# batteryholder3S2P_revA.net
KiCad netlist of a schematic drawn in EAGLE
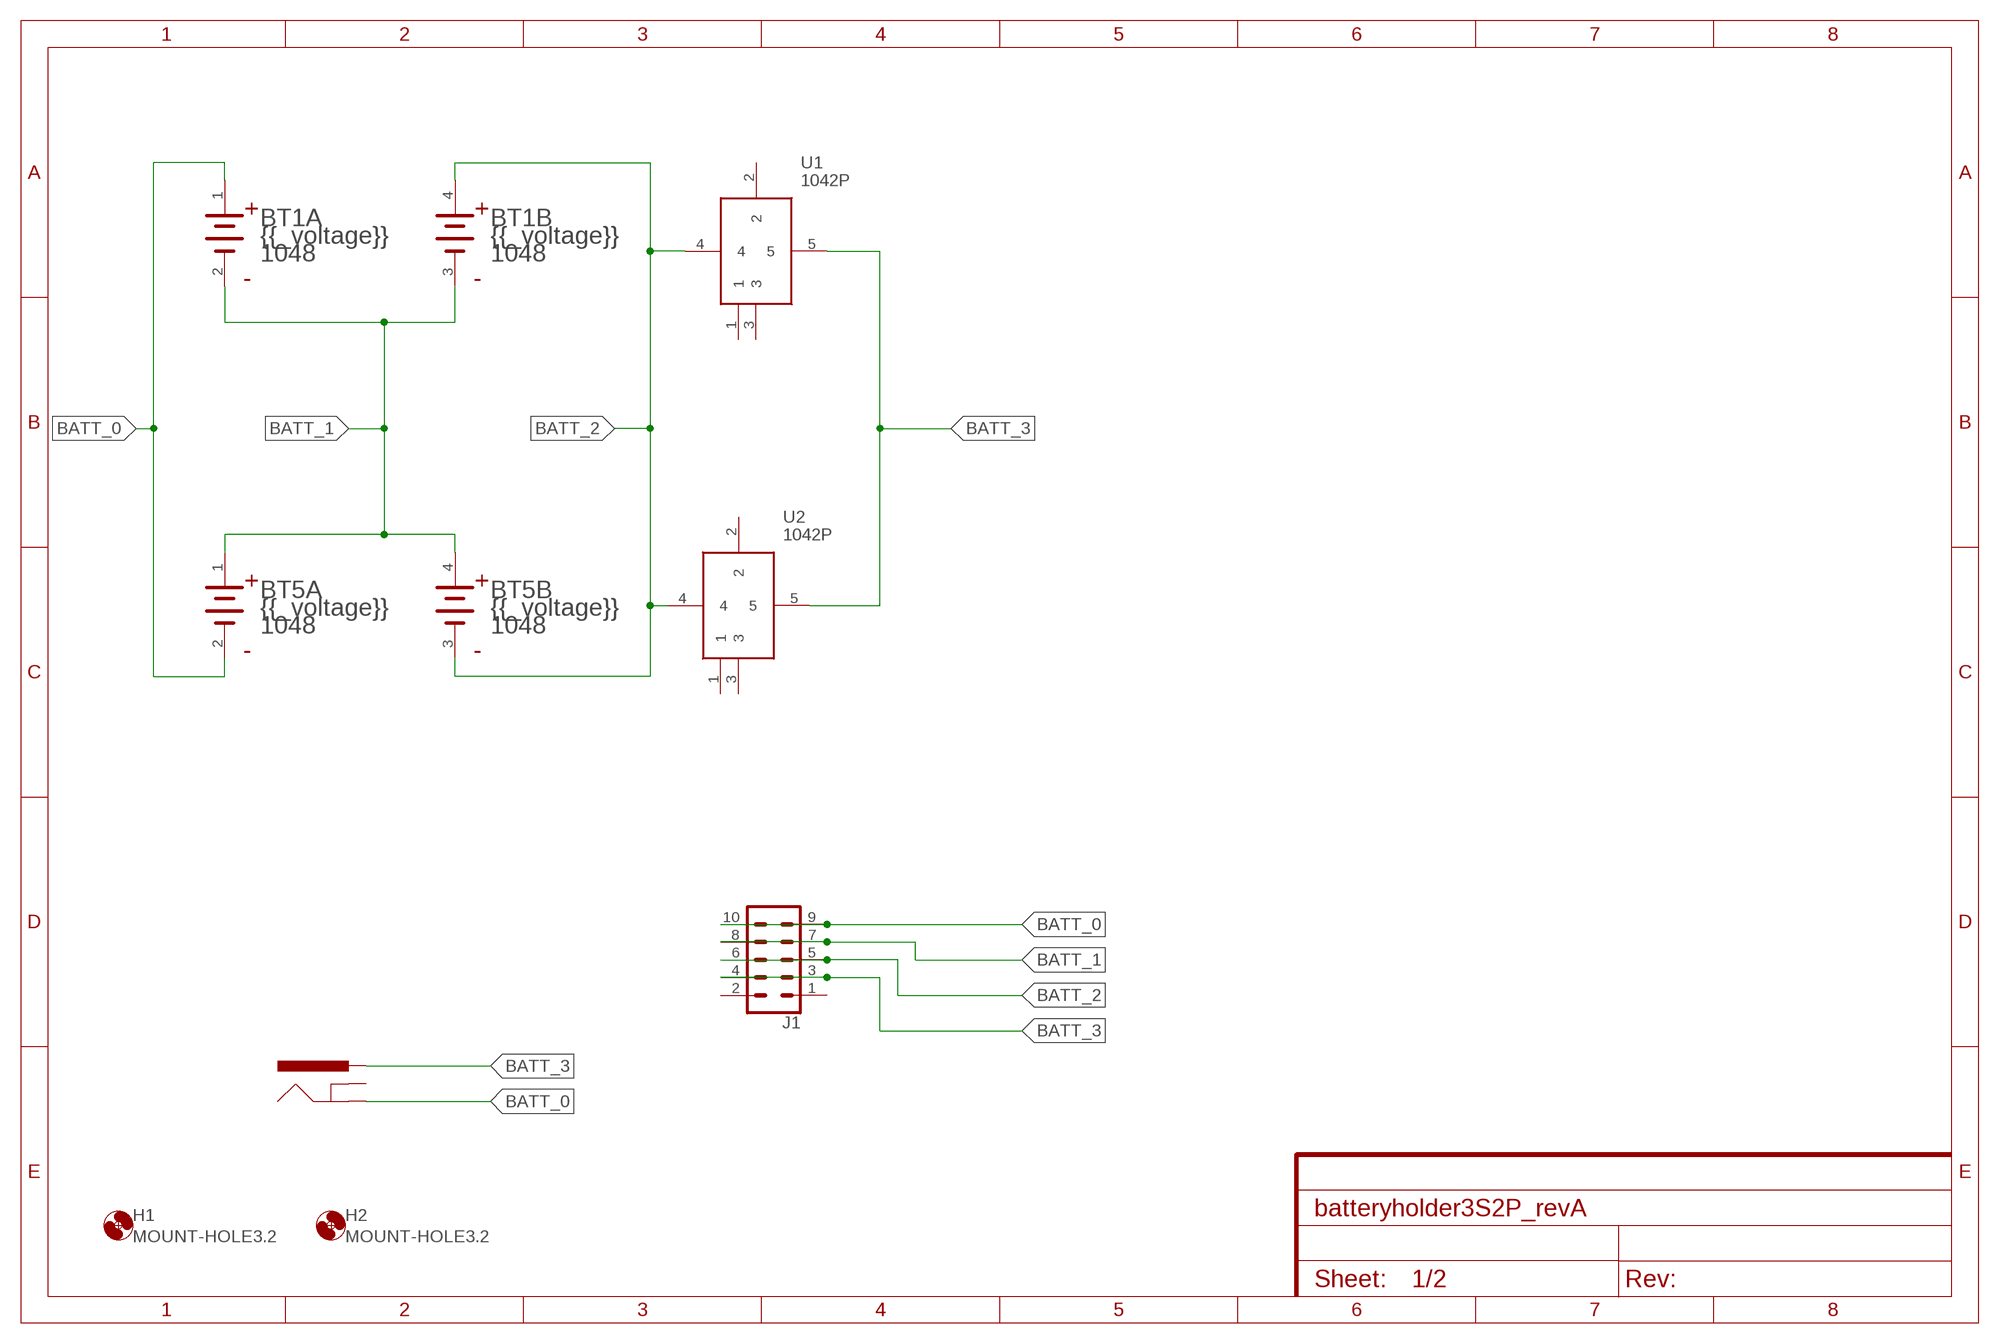
[diagram p0: schematic, sheet 1]

(export (version "E")
  (design (tool "Eeschema 10.0.6"))
  (components
    (comp (ref "BT1")
      (value "KEYSTONE_1048KEYSTONE_1048_0_0")
      (footprint "eagle-import:KEYSTONE_1048_0")
      (fields
        (field (name "DIGIKEY_PART_NUMBER") "36-1048-ND")
        (field (name "MF") "Keystone")
        (field (name "MOUSER_PART_NUMBER") "534-1048")
      )
      (libsource (lib "eagle-import") (part "KEYSTONE_1048KEYSTONE_1048_0_0"))
    )
    (comp (ref "BT5")
      (value "KEYSTONE_1048KEYSTONE_1048_0_0")
      (footprint "eagle-import:KEYSTONE_1048_0")
      (fields
        (field (name "DIGIKEY_PART_NUMBER") "36-1048-ND")
        (field (name "MF") "Keystone")
        (field (name "MOUSER_PART_NUMBER") "534-1048")
      )
      (libsource (lib "eagle-import") (part "KEYSTONE_1048KEYSTONE_1048_0_0"))
    )
    (comp (ref "H1")
      (value "MOUNT-HOLE3.2")
      (footprint "eagle-import:3,2")
      (libsource (lib "eagle-import") (part "MOUNT-HOLE3.2"))
    )
    (comp (ref "H2")
      (value "MOUNT-HOLE3.2")
      (footprint "eagle-import:3,2")
      (libsource (lib "eagle-import") (part "MOUNT-HOLE3.2"))
    )
    (comp (ref "J1")
      (value "CONN_05X2SHD")
      (footprint "eagle-import:2X5-SHROUDED")
      (libsource (lib "eagle-import") (part "CONN_05X2SHD"))
    )
    (comp (ref "J3")
      (value "POWER_JACKPTH_BREAD")
      (footprint "eagle-import:POWER_JACK_PTH_BREAD")
      (libsource (lib "eagle-import") (part "POWER_JACKPTH_BREAD"))
    )
    (comp (ref "U1")
      (value "1042P")
      (footprint "eagle-import:1042P")
      (fields (field (name "MOUSER_PART_NUMBER") "534-1042P"))
      (libsource (lib "eagle-import") (part "1042P"))
    )
    (comp (ref "U2")
      (value "1042P")
      (footprint "eagle-import:1042P")
      (fields (field (name "MOUSER_PART_NUMBER") "534-1042P"))
      (libsource (lib "eagle-import") (part "1042P"))
    )
  )
  (nets
    (net (code "1") (name "BATT_0") (class "Default")
      (node (ref "BT1") (pin "1") (pinfunction "1_ANODE_1") (pintype "passive"))
      (node (ref "BT5") (pin "2") (pinfunction "1_CATHODE_2") (pintype "passive"))
      (node (ref "J1") (pin "10") (pinfunction "10_10") (pintype "passive"))
      (node (ref "J1") (pin "9") (pinfunction "9_9") (pintype "passive"))
      (node (ref "J3") (pin "GND") (pinfunction "GND_GND") (pintype "bidirectional"))
    )
    (net (code "2") (name "BATT_1") (class "Default")
      (node (ref "BT1") (pin "2") (pinfunction "1_CATHODE_2") (pintype "passive"))
      (node (ref "BT1") (pin "3") (pinfunction "2_CATHODE_3") (pintype "passive"))
      (node (ref "BT5") (pin "1") (pinfunction "1_ANODE_1") (pintype "passive"))
      (node (ref "BT5") (pin "4") (pinfunction "2_ANODE_4") (pintype "passive"))
      (node (ref "J1") (pin "7") (pinfunction "7_7") (pintype "passive"))
      (node (ref "J1") (pin "8") (pinfunction "8_8") (pintype "passive"))
    )
    (net (code "3") (name "BATT_2") (class "Default")
      (node (ref "BT1") (pin "4") (pinfunction "2_ANODE_4") (pintype "passive"))
      (node (ref "BT5") (pin "3") (pinfunction "2_CATHODE_3") (pintype "passive"))
      (node (ref "J1") (pin "5") (pinfunction "5_5") (pintype "passive"))
      (node (ref "J1") (pin "6") (pinfunction "6_6") (pintype "passive"))
      (node (ref "U1") (pin "4") (pinfunction "4_4") (pintype "bidirectional"))
      (node (ref "U2") (pin "4") (pinfunction "4_4") (pintype "bidirectional"))
    )
    (net (code "4") (name "BATT_3") (class "Default")
      (node (ref "J1") (pin "3") (pinfunction "3_3") (pintype "passive"))
      (node (ref "J1") (pin "4") (pinfunction "4_4") (pintype "passive"))
      (node (ref "J3") (pin "PWR") (pinfunction "PWR_PWR") (pintype "bidirectional"))
      (node (ref "U1") (pin "5") (pinfunction "5_5") (pintype "bidirectional"))
      (node (ref "U2") (pin "5") (pinfunction "5_5") (pintype "bidirectional"))
    )
    (net (code "5") (name "unconnected-(J1-Pad1)") (class "Default")
      (node (ref "J1") (pin "1") (pinfunction "1_1") (pintype "passive"))
    )
    (net (code "6") (name "unconnected-(J1-Pad2)") (class "Default")
      (node (ref "J1") (pin "2") (pinfunction "2_2") (pintype "passive"))
    )
    (net (code "7") (name "unconnected-(J3-PadGNDBREAK)") (class "Default")
      (node (ref "J3") (pin "GNDBREAK") (pinfunction "GNDBREAK_GNDBREAK") (pintype "bidirectional"))
    )
    (net (code "8") (name "unconnected-(U1-Pad1)") (class "Default")
      (node (ref "U1") (pin "1") (pinfunction "1_1") (pintype "bidirectional"))
    )
    (net (code "9") (name "unconnected-(U1-Pad2)") (class "Default")
      (node (ref "U1") (pin "2") (pinfunction "2_2") (pintype "bidirectional"))
    )
    (net (code "10") (name "unconnected-(U1-Pad3)") (class "Default")
      (node (ref "U1") (pin "3") (pinfunction "3_3") (pintype "bidirectional"))
    )
    (net (code "11") (name "unconnected-(U2-Pad1)") (class "Default")
      (node (ref "U2") (pin "1") (pinfunction "1_1") (pintype "bidirectional"))
    )
    (net (code "12") (name "unconnected-(U2-Pad2)") (class "Default")
      (node (ref "U2") (pin "2") (pinfunction "2_2") (pintype "bidirectional"))
    )
    (net (code "13") (name "unconnected-(U2-Pad3)") (class "Default")
      (node (ref "U2") (pin "3") (pinfunction "3_3") (pintype "bidirectional"))
    )
  )
)
